# psu.net
KiCad netlist of a schematic drawn in Altium Designer
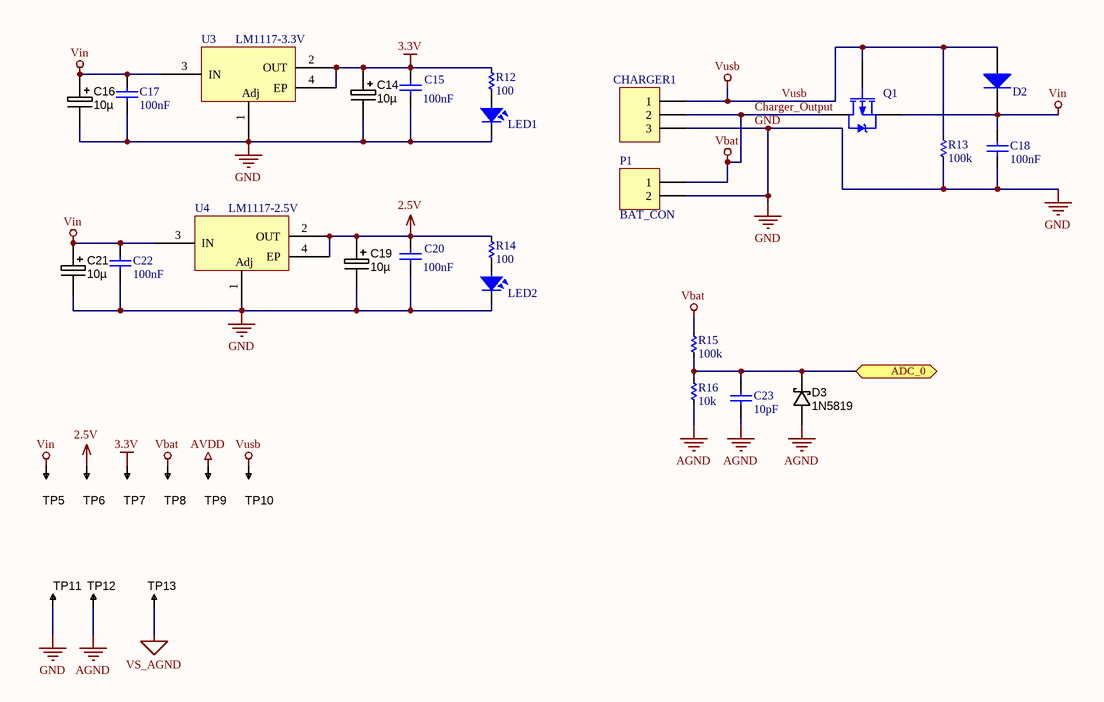
[diagram p0: psu.SchDoc]

(export (version "E")
  (design (tool "Eeschema 10.0.6"))
  (components
    (comp (ref "C14")
      (value "10µ")
      (footprint "CAPMP3216X180N")
      (description "Capacitor SMD Tantalum 68uF 10% 6.3V EIA 3216-18")
      (fields (field (name "TOLERANCE") "±10%"))
      (libsource (lib "PBL - Capacitors") (part "CAPT_68u_3216_6V3"))
    )
    (comp (ref "C15")
      (value "100nF")
      (footprint "CAPC1608X90N")
      (description "Capacitor (Semiconductor SIM Model)")
      (fields (field (name "Comment") "Cap Semi") (field (name "PUBLISHER") "Altium Limited"))
      (libsource (lib "Mylib") (part "Cap Semi"))
    )
    (comp (ref "C16")
      (value "10µ")
      (footprint "CAPMP3216X180N")
      (description "Capacitor SMD Tantalum 68uF 10% 6.3V EIA 3216-18")
      (fields (field (name "TOLERANCE") "±10%"))
      (libsource (lib "PBL - Capacitors") (part "CAPT_68u_3216_6V3"))
    )
    (comp (ref "C17")
      (value "100nF")
      (footprint "CAPC1608X90N")
      (description "Capacitor (Semiconductor SIM Model)")
      (fields (field (name "Comment") "Cap Semi") (field (name "PUBLISHER") "Altium Limited"))
      (libsource (lib "Mylib") (part "Cap Semi"))
    )
    (comp (ref "C18")
      (value "100nF")
      (footprint "CAPC1608X90N")
      (description "Capacitor (Semiconductor SIM Model)")
      (fields (field (name "Comment") "Cap Semi") (field (name "PUBLISHER") "Altium Limited"))
      (libsource (lib "Mylib") (part "Cap Semi"))
    )
    (comp (ref "C19")
      (value "10µ")
      (footprint "CAPMP3216X180N")
      (description "Capacitor SMD Tantalum 68uF 10% 6.3V EIA 3216-18")
      (fields (field (name "TOLERANCE") "±10%"))
      (libsource (lib "PBL - Capacitors") (part "CAPT_68u_3216_6V3"))
    )
    (comp (ref "C20")
      (value "100nF")
      (footprint "CAPC1608X90N")
      (description "Capacitor (Semiconductor SIM Model)")
      (fields (field (name "Comment") "Cap Semi") (field (name "PUBLISHER") "Altium Limited"))
      (libsource (lib "Mylib") (part "Cap Semi"))
    )
    (comp (ref "C21")
      (value "10µ")
      (footprint "CAPMP3216X180N")
      (description "Capacitor SMD Tantalum 68uF 10% 6.3V EIA 3216-18")
      (fields (field (name "TOLERANCE") "±10%"))
      (libsource (lib "PBL - Capacitors") (part "CAPT_68u_3216_6V3"))
    )
    (comp (ref "C22")
      (value "100nF")
      (footprint "CAPC1608X90N")
      (description "Capacitor (Semiconductor SIM Model)")
      (fields (field (name "Comment") "Cap Semi") (field (name "PUBLISHER") "Altium Limited"))
      (libsource (lib "Mylib") (part "Cap Semi"))
    )
    (comp (ref "C23")
      (value "10pF")
      (footprint "CAPC1608X90N")
      (description "Capacitor (Semiconductor SIM Model)")
      (fields (field (name "Comment") "Cap Semi") (field (name "PUBLISHER") "Altium Limited"))
      (libsource (lib "Mylib") (part "Cap Semi"))
    )
    (comp (ref "CHARGER1")
      (value "3-Pin connector")
      (footprint "HDR1X3")
      (libsource (lib "Mylib") (part "Header 3"))
    )
    (comp (ref "D2")
      (value "Diode")
      (footprint "SMD Diode")
      (description "SS14, Schottky Diode")
      (fields (field (name "PUBLISHER") "Altium Limited"))
      (libsource (lib "NmiAltiumLibrary") (part "Diode"))
    )
    (comp (ref "D3")
      (value "DIODE_SCHOTTKY_40V_1A")
      (footprint "SOD123")
      (description "Diode Schottky SMD 40V 1A SOD123")
      (fields (field (name "MANUFACTURER PART NUMBER 1") "1N5819"))
      (libsource (lib "PBL - Diodes") (part "DIODE_SCHOTTKY_40V_1A"))
    )
    (comp (ref "LED1") (value "LED") (footprint "LED-0805-Red") (libsource (lib "Mylib") (part "LED SMD")))
    (comp (ref "LED2") (value "LED") (footprint "LED-0805-Red") (libsource (lib "Mylib") (part "LED SMD")))
    (comp (ref "P1")
      (value "BAT_CON")
      (footprint "HDR1X2")
      (description "Header, 2-Pin")
      (fields (field (name "PUBLISHER") "Altium Limited"))
      (libsource (lib "Miscellaneous Connectors") (part "Header 2"))
    )
    (comp (ref "Q1")
      (value "IRLML6402")
      (footprint "SOT-23B_N")
      (fields (field (name "PUBLISHER") "Altium Limited"))
      (libsource (lib "Mylib") (part "IRLML6402"))
    )
    (comp (ref "R12")
      (value "100")
      (footprint "RES-SMD-0603")
      (description "Resistor")
      (fields
        (field (name "MANUFACTURER") "Generic Components")
        (field (name "Comment") "Res")
        (field (name "PUBLISHER") "Altium Hobart Technology Centre")
      )
      (libsource (lib "Mylib") (part "Res-SMD"))
    )
    (comp (ref "R13")
      (value "100k")
      (footprint "RES-SMD-1206")
      (description "Resistor")
      (fields
        (field (name "MANUFACTURER") "Generic Components")
        (field (name "Comment") "Res")
        (field (name "PUBLISHER") "Altium Hobart Technology Centre")
      )
      (libsource (lib "Mylib") (part "Res-SMD"))
    )
    (comp (ref "R14")
      (value "100")
      (footprint "RES-SMD-0603")
      (description "Resistor")
      (fields
        (field (name "MANUFACTURER") "Generic Components")
        (field (name "Comment") "Res")
        (field (name "PUBLISHER") "Altium Hobart Technology Centre")
      )
      (libsource (lib "Mylib") (part "Res-SMD"))
    )
    (comp (ref "R15")
      (value "100k")
      (footprint "RES-SMD-0805")
      (description "Resistor")
      (fields
        (field (name "MANUFACTURER") "Generic Components")
        (field (name "Comment") "Res")
        (field (name "PUBLISHER") "Altium Hobart Technology Centre")
      )
      (libsource (lib "Mylib") (part "Res-SMD"))
    )
    (comp (ref "R16")
      (value "10k")
      (footprint "RES-SMD-0805")
      (description "Resistor")
      (fields
        (field (name "MANUFACTURER") "Generic Components")
        (field (name "Comment") "Res")
        (field (name "PUBLISHER") "Altium Hobart Technology Centre")
      )
      (libsource (lib "Mylib") (part "Res-SMD"))
    )
    (comp (ref "TP5")
      (value "TESTPOINT")
      (footprint "TP-R60")
      (description "SMD test pin")
      (libsource (lib "PBL - Test Points") (part "TESTPOINT"))
    )
    (comp (ref "TP6")
      (value "TESTPOINT")
      (footprint "TP-R60")
      (description "SMD test pin")
      (libsource (lib "PBL - Test Points") (part "TESTPOINT"))
    )
    (comp (ref "TP7")
      (value "TESTPOINT")
      (footprint "TP-R60")
      (description "SMD test pin")
      (libsource (lib "PBL - Test Points") (part "TESTPOINT"))
    )
    (comp (ref "TP8")
      (value "TESTPOINT")
      (footprint "TP-R60")
      (description "SMD test pin")
      (libsource (lib "PBL - Test Points") (part "TESTPOINT"))
    )
    (comp (ref "TP9")
      (value "TESTPOINT")
      (footprint "TP-R60")
      (description "SMD test pin")
      (libsource (lib "PBL - Test Points") (part "TESTPOINT"))
    )
    (comp (ref "TP10")
      (value "TESTPOINT")
      (footprint "TP-R60")
      (description "SMD test pin")
      (libsource (lib "PBL - Test Points") (part "TESTPOINT"))
    )
    (comp (ref "TP11")
      (value "TESTPOINT")
      (footprint "TP-R60")
      (description "SMD test pin")
      (libsource (lib "PBL - Test Points") (part "TESTPOINT"))
    )
    (comp (ref "TP12")
      (value "TESTPOINT")
      (footprint "TP-R60")
      (description "SMD test pin")
      (libsource (lib "PBL - Test Points") (part "TESTPOINT"))
    )
    (comp (ref "TP13")
      (value "TESTPOINT")
      (footprint "TP-R60")
      (description "SMD test pin")
      (libsource (lib "PBL - Test Points") (part "TESTPOINT"))
    )
    (comp (ref "U3")
      (value "LM1117-3.3V")
      (footprint "SOT230P700X180-4N")
      (libsource (lib "NmiAltiumLibrary") (part "LM1117-4N"))
    )
    (comp (ref "U4")
      (value "LM1117-2.5V")
      (footprint "SOT230P700X180-4N")
      (libsource (lib "NmiAltiumLibrary") (part "LM1117-4N"))
    )
  )
  (nets
    (net (code "1") (name "/ADC_0") (class "Default")
      (node (ref "C23") (pin "2") (pinfunction "2_2") (pintype "passive"))
      (node (ref "D3") (pin "K") (pinfunction "K_K") (pintype "passive"))
      (node (ref "R15") (pin "2") (pinfunction "2_2") (pintype "passive"))
      (node (ref "R16") (pin "1") (pinfunction "1_1") (pintype "passive"))
    )
    (net (code "2") (name "2.5V") (class "Default")
      (node (ref "C19") (pin "1") (pintype "passive"))
      (node (ref "C20") (pin "2") (pinfunction "2_2") (pintype "passive"))
      (node (ref "R14") (pin "1") (pinfunction "1_1") (pintype "passive"))
      (node (ref "TP6") (pin "1") (pintype "passive"))
      (node (ref "U4") (pin "2") (pinfunction "OUT_2") (pintype "passive"))
      (node (ref "U4") (pin "4") (pinfunction "EP_4") (pintype "passive"))
    )
    (net (code "3") (name "3.3V") (class "Default")
      (node (ref "C14") (pin "1") (pintype "passive"))
      (node (ref "C15") (pin "2") (pinfunction "2_2") (pintype "passive"))
      (node (ref "R12") (pin "1") (pinfunction "1_1") (pintype "passive"))
      (node (ref "TP7") (pin "1") (pintype "passive"))
      (node (ref "U3") (pin "2") (pinfunction "OUT_2") (pintype "passive"))
      (node (ref "U3") (pin "4") (pinfunction "EP_4") (pintype "passive"))
    )
    (net (code "4") (name "AGND") (class "Default")
      (node (ref "C23") (pin "1") (pinfunction "1_1") (pintype "passive"))
      (node (ref "D3") (pin "A") (pinfunction "A_A") (pintype "passive"))
      (node (ref "R16") (pin "2") (pinfunction "2_2") (pintype "passive"))
      (node (ref "TP12") (pin "1") (pintype "passive"))
    )
    (net (code "5") (name "AVDD") (class "Default") (node (ref "TP9") (pin "1") (pintype "passive")))
    (net (code "6") (name "GND") (class "Default")
      (node (ref "C14") (pin "2") (pintype "passive"))
      (node (ref "C15") (pin "1") (pinfunction "1_1") (pintype "passive"))
      (node (ref "C16") (pin "2") (pintype "passive"))
      (node (ref "C17") (pin "1") (pinfunction "1_1") (pintype "passive"))
      (node (ref "C18") (pin "1") (pinfunction "1_1") (pintype "passive"))
      (node (ref "C19") (pin "2") (pintype "passive"))
      (node (ref "C20") (pin "1") (pinfunction "1_1") (pintype "passive"))
      (node (ref "C21") (pin "2") (pintype "passive"))
      (node (ref "C22") (pin "1") (pinfunction "1_1") (pintype "passive"))
      (node (ref "CHARGER1") (pin "3") (pinfunction "3_3") (pintype "passive"))
      (node (ref "LED1") (pin "2") (pinfunction "2_2") (pintype "passive"))
      (node (ref "LED2") (pin "2") (pinfunction "2_2") (pintype "passive"))
      (node (ref "P1") (pin "2") (pinfunction "2_2") (pintype "passive"))
      (node (ref "R13") (pin "2") (pinfunction "2_2") (pintype "passive"))
      (node (ref "TP11") (pin "1") (pintype "passive"))
      (node (ref "U3") (pin "1") (pinfunction "ADJ_1") (pintype "passive"))
      (node (ref "U4") (pin "1") (pinfunction "ADJ_1") (pintype "passive"))
    )
    (net (code "7") (name "Net-(LED1-Pad1)") (class "Default")
      (node (ref "LED1") (pin "1") (pinfunction "1_1") (pintype "passive"))
      (node (ref "R12") (pin "2") (pinfunction "2_2") (pintype "passive"))
    )
    (net (code "8") (name "Net-(LED2-Pad1)") (class "Default")
      (node (ref "LED2") (pin "1") (pinfunction "1_1") (pintype "passive"))
      (node (ref "R14") (pin "2") (pinfunction "2_2") (pintype "passive"))
    )
    (net (code "9") (name "VS_AGND") (class "Default") (node (ref "TP13") (pin "1") (pintype "passive")))
    (net (code "10") (name "Vbat") (class "Default")
      (node (ref "CHARGER1") (pin "2") (pinfunction "2_2") (pintype "passive"))
      (node (ref "P1") (pin "1") (pinfunction "1_1") (pintype "passive"))
      (node (ref "Q1") (pin "3") (pinfunction "D_3") (pintype "passive"))
      (node (ref "R15") (pin "1") (pinfunction "1_1") (pintype "passive"))
      (node (ref "TP8") (pin "1") (pintype "passive"))
    )
    (net (code "11") (name "Vin") (class "Default")
      (node (ref "C16") (pin "1") (pintype "passive"))
      (node (ref "C17") (pin "2") (pinfunction "2_2") (pintype "passive"))
      (node (ref "C18") (pin "2") (pinfunction "2_2") (pintype "passive"))
      (node (ref "C21") (pin "1") (pintype "passive"))
      (node (ref "C22") (pin "2") (pinfunction "2_2") (pintype "passive"))
      (node (ref "D2") (pin "2") (pinfunction "K_2") (pintype "passive"))
      (node (ref "Q1") (pin "2") (pinfunction "S_2") (pintype "passive"))
      (node (ref "TP5") (pin "1") (pintype "passive"))
      (node (ref "U3") (pin "3") (pinfunction "IN_3") (pintype "passive"))
      (node (ref "U4") (pin "3") (pinfunction "IN_3") (pintype "passive"))
    )
    (net (code "12") (name "Vusb") (class "Default")
      (node (ref "CHARGER1") (pin "1") (pinfunction "1_1") (pintype "passive"))
      (node (ref "D2") (pin "1") (pinfunction "A_1") (pintype "passive"))
      (node (ref "Q1") (pin "1") (pinfunction "G_1") (pintype "passive"))
      (node (ref "R13") (pin "1") (pinfunction "1_1") (pintype "passive"))
      (node (ref "TP10") (pin "1") (pintype "passive"))
    )
  )
)
